# 13hdmi_lcd.net
KiCad netlist of a schematic drawn in Altium Designer
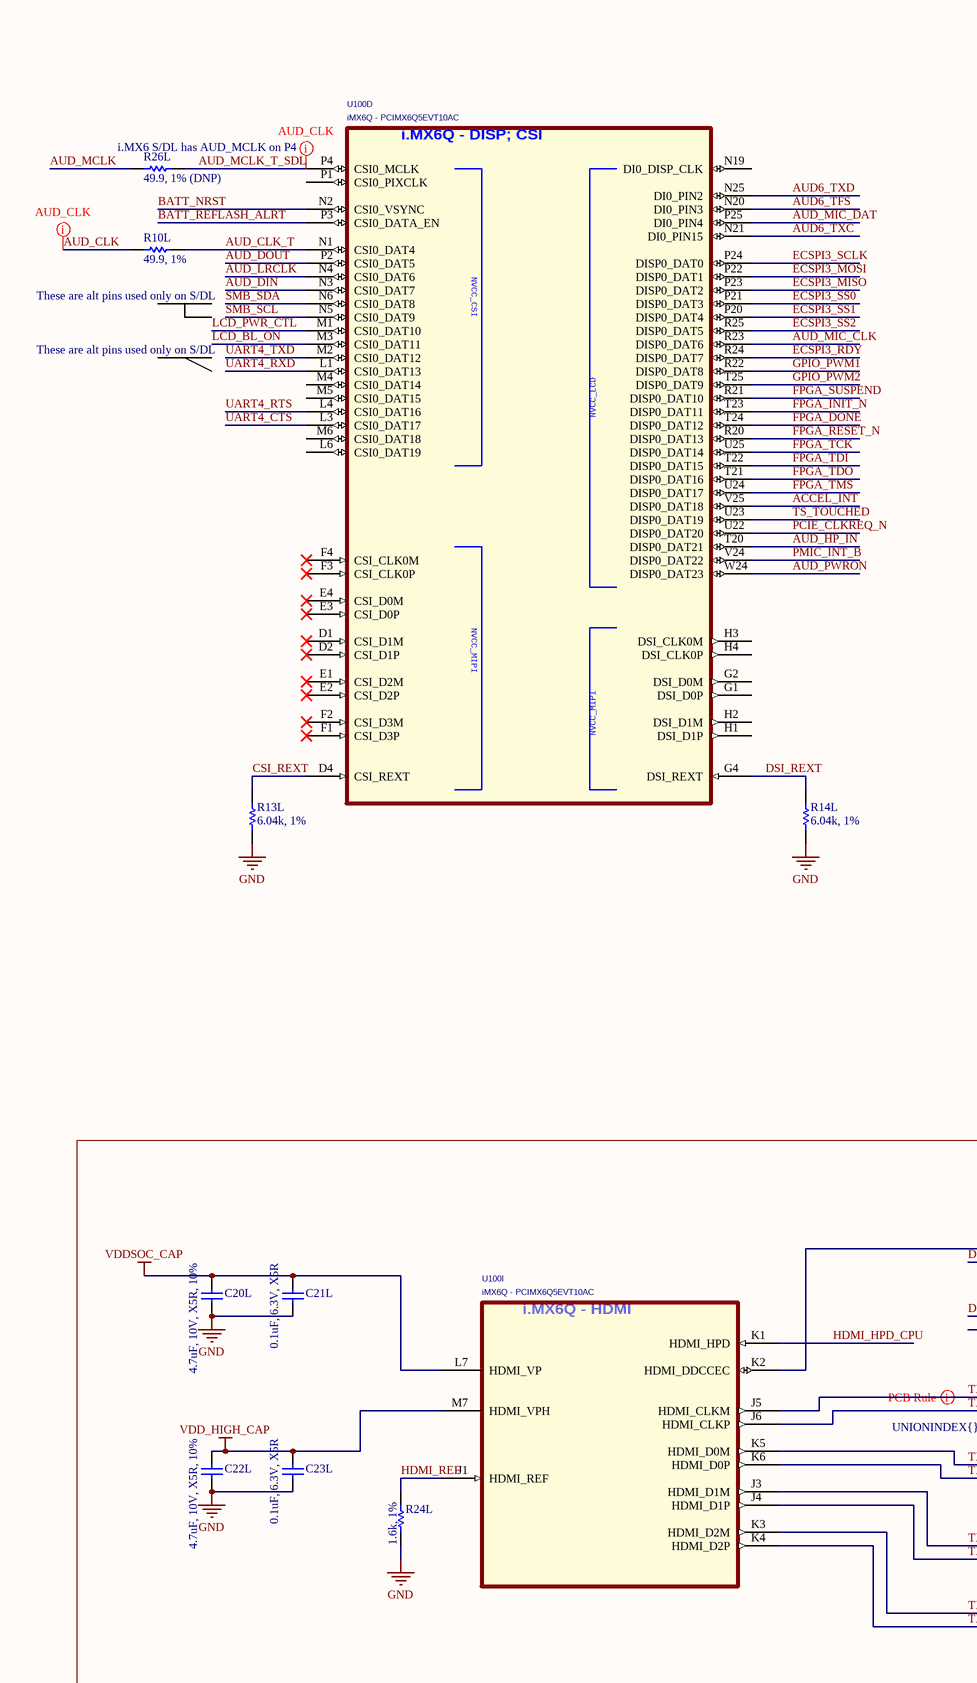
[diagram p0: 13hdmi_lcd.SchDoc, left]
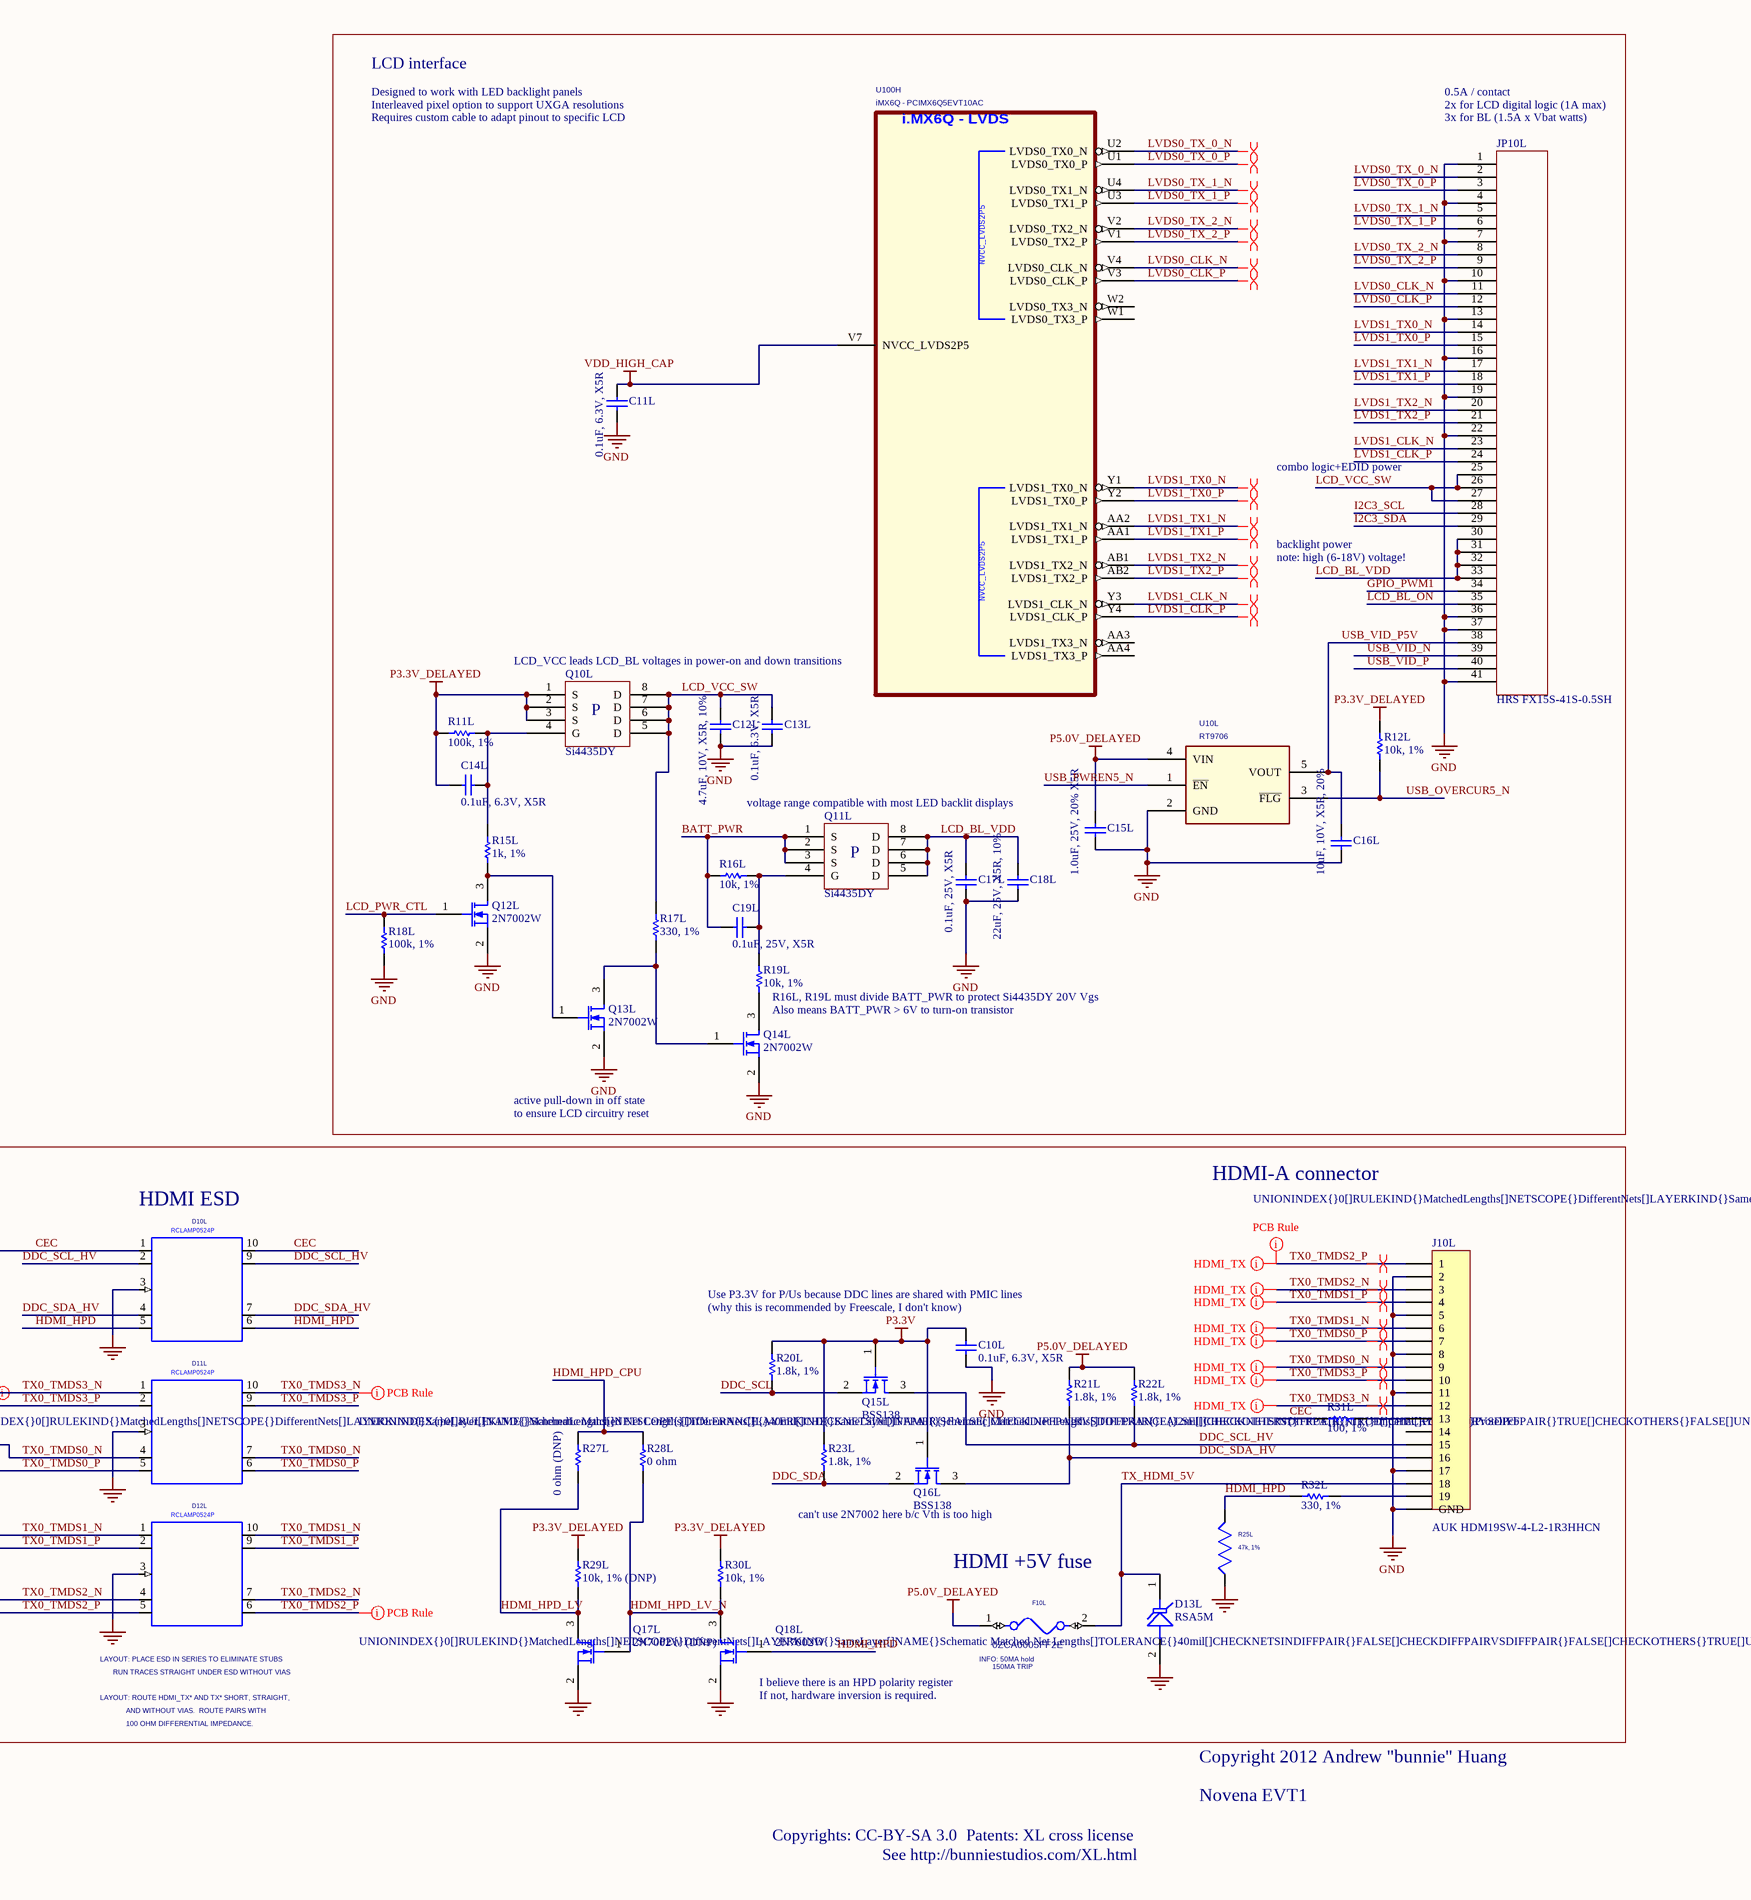
[diagram p1: 13hdmi_lcd.SchDoc, right]

(export (version "E")
  (design (tool "Eeschema 10.0.6"))
  (components
    (comp (ref "C10L")
      (value "0.1uF, 6.3V, X5R")
      (footprint "CAPC0603N_B")
      (description "Capacitor (Semiconductor SIM Model)")
      (fields (field (name "PUBLISHER") "Altium Limited"))
      (libsource (lib "Miscellaneous Devices") (part "Cap Semi"))
    )
    (comp (ref "C11L")
      (value "0.1uF, 6.3V, X5R")
      (footprint "CAPC0603N_B")
      (description "Capacitor (Semiconductor SIM Model)")
      (fields (field (name "PUBLISHER") "Altium Limited"))
      (libsource (lib "Miscellaneous Devices") (part "Cap Semi"))
    )
    (comp (ref "C12L")
      (value "4.7uF, 10V, X5R, 10%")
      (footprint "CAPC1608N")
      (description "Capacitor (Semiconductor SIM Model)")
      (fields (field (name "PUBLISHER") "Altium Limited"))
      (libsource (lib "Miscellaneous Devices") (part "Cap Semi"))
    )
    (comp (ref "C13L")
      (value "0.1uF, 6.3V, X5R")
      (footprint "CAPC0603N_B")
      (description "Capacitor (Semiconductor SIM Model)")
      (fields (field (name "PUBLISHER") "Altium Limited"))
      (libsource (lib "Miscellaneous Devices") (part "Cap Semi"))
    )
    (comp (ref "C14L")
      (value "0.1uF, 6.3V, X5R")
      (footprint "CAPC0603N_B")
      (description "Capacitor (Semiconductor SIM Model)")
      (fields (field (name "PUBLISHER") "Altium Limited"))
      (libsource (lib "Miscellaneous Devices") (part "Cap Semi"))
    )
    (comp (ref "C15L")
      (value "1.0uF, 25V, 20% X5R")
      (footprint "CAPC1608N")
      (description "Capacitor (Semiconductor SIM Model)")
      (fields (field (name "PUBLISHER") "Altium Limited"))
      (libsource (lib "Miscellaneous Devices") (part "Cap Semi"))
    )
    (comp (ref "C16L")
      (value "10uF, 10V, X5R, 20%")
      (footprint "CAPC1608N")
      (description "Capacitor (Semiconductor SIM Model)")
      (fields (field (name "PUBLISHER") "Altium Limited"))
      (libsource (lib "Miscellaneous Devices") (part "Cap Semi"))
    )
    (comp (ref "C17L")
      (value "0.1uF, 25V, X5R")
      (footprint "CAPC1005N")
      (description "Capacitor (Semiconductor SIM Model)")
      (fields (field (name "PUBLISHER") "Altium Limited"))
      (libsource (lib "Miscellaneous Devices") (part "Cap Semi"))
    )
    (comp (ref "C18L")
      (value "22uF, 25V, X5R, 10%")
      (footprint "CAPC3225N")
      (description "Capacitor (Semiconductor SIM Model)")
      (fields (field (name "PUBLISHER") "Altium Limited"))
      (libsource (lib "Miscellaneous Devices") (part "Cap Semi"))
    )
    (comp (ref "C19L")
      (value "0.1uF, 25V, X5R")
      (footprint "CAPC1005N")
      (description "Capacitor (Semiconductor SIM Model)")
      (fields (field (name "PUBLISHER") "Altium Limited"))
      (libsource (lib "Miscellaneous Devices") (part "Cap Semi"))
    )
    (comp (ref "C20L")
      (value "4.7uF, 10V, X5R, 10%")
      (footprint "CAPC1608N_HD")
      (description "Capacitor (Semiconductor SIM Model)")
      (fields (field (name "PUBLISHER") "Altium Limited"))
      (libsource (lib "Miscellaneous Devices") (part "Cap Semi"))
    )
    (comp (ref "C21L")
      (value "0.1uF, 6.3V, X5R")
      (footprint "CAPC0603N_B")
      (description "Capacitor (Semiconductor SIM Model)")
      (fields (field (name "PUBLISHER") "Altium Limited"))
      (libsource (lib "Miscellaneous Devices") (part "Cap Semi"))
    )
    (comp (ref "C22L")
      (value "4.7uF, 10V, X5R, 10%")
      (footprint "CAPC1608N_HD")
      (description "Capacitor (Semiconductor SIM Model)")
      (fields (field (name "PUBLISHER") "Altium Limited"))
      (libsource (lib "Miscellaneous Devices") (part "Cap Semi"))
    )
    (comp (ref "C23L")
      (value "0.1uF, 6.3V, X5R")
      (footprint "CAPC0603N_B")
      (description "Capacitor (Semiconductor SIM Model)")
      (fields (field (name "PUBLISHER") "Altium Limited"))
      (libsource (lib "Miscellaneous Devices") (part "Cap Semi"))
    )
    (comp (ref "D10L")
      (value "RCLAMP0524P")
      (fields (field (name "PART_NUMBER") "V00004-001"))
      (libsource (lib "*") (part "RCLAMP0524P"))
    )
    (comp (ref "D11L")
      (value "RCLAMP0524P")
      (fields (field (name "PART_NUMBER") "V00004-001"))
      (libsource (lib "*") (part "RCLAMP0524P"))
    )
    (comp (ref "D12L")
      (value "RCLAMP0524P")
      (fields (field (name "PART_NUMBER") "V00004-001"))
      (libsource (lib "*") (part "RCLAMP0524P"))
    )
    (comp (ref "D13L")
      (value "RSA5M")
      (footprint "SOD123/X.85")
      (description "Tranzorb")
      (fields (field (name "PUBLISHER") "Altium Limited"))
      (libsource (lib "Miscellaneous Devices") (part "Tranzorb"))
    )
    (comp (ref "F10L")
      (value "0ZCA0005FF2E")
      (description "BelFuse, 50mA hold, 150mA trip")
      (fields (field (name "PART_NUMBER") "M00014-001"))
      (libsource (lib "*") (part "FUSE0805"))
    )
    (comp (ref "J10L")
      (value "AUK HDM19SW-4-L2-1R3HHCN")
      (footprint "MOLEX_47151-0001")
      (description "Molex HDMI connector, Type A")
      (fields (field (name "PUBLISHER") "Altium Limited"))
      (libsource (lib "Miscellaneous Connectors") (part "Header 19"))
    )
    (comp (ref "JP10L")
      (value "HRS FX15S-41S-0.5SH")
      (footprint "HRS_FX15S-41S-0.5SH")
      (description "41-pin header")
      (libsource (lib "commonsch") (part "HRS_FX15S-41S-0.5SH"))
    )
    (comp (ref "Q10L")
      (value "Si4435DY")
      (footprint "SOIC127P600-8AN")
      (description "Singre P-channel FET, 8A, 30V")
      (libsource (lib "commonsch") (part "Si4435DY"))
    )
    (comp (ref "Q11L")
      (value "Si4435DY")
      (footprint "SOIC127P600-8AN")
      (description "Singre P-channel FET, 8A, 30V")
      (libsource (lib "commonsch") (part "Si4435DY"))
    )
    (comp (ref "Q12L")
      (value "2N7002W")
      (footprint "SOT323-3AN")
      (description "N-Channel MOSFET")
      (fields (field (name "PUBLISHER") "Altium Limited"))
      (libsource (lib "Miscellaneous Devices") (part "MOSFET-N"))
    )
    (comp (ref "Q13L")
      (value "2N7002W")
      (footprint "SOT323-3AN")
      (description "N-Channel MOSFET")
      (fields (field (name "PUBLISHER") "Altium Limited"))
      (libsource (lib "Miscellaneous Devices") (part "MOSFET-N"))
    )
    (comp (ref "Q14L")
      (value "2N7002W")
      (footprint "SOT323-3AN")
      (description "N-Channel MOSFET")
      (fields (field (name "PUBLISHER") "Altium Limited"))
      (libsource (lib "Miscellaneous Devices") (part "MOSFET-N"))
    )
    (comp (ref "Q15L")
      (value "BSS138")
      (footprint "SOT23-3N")
      (description "N-Channel MOSFET")
      (fields (field (name "PUBLISHER") "Altium Limited"))
      (libsource (lib "Miscellaneous Devices") (part "MOSFET-N"))
    )
    (comp (ref "Q16L")
      (value "BSS138")
      (footprint "SOT23-3N")
      (description "N-Channel MOSFET")
      (fields (field (name "PUBLISHER") "Altium Limited"))
      (libsource (lib "Miscellaneous Devices") (part "MOSFET-N"))
    )
    (comp (ref "Q17L")
      (value "2N7002W (DNP)")
      (footprint "SOT323-3AN")
      (description "N-Channel MOSFET")
      (fields (field (name "PUBLISHER") "Altium Limited"))
      (libsource (lib "Miscellaneous Devices") (part "MOSFET-N"))
    )
    (comp (ref "Q18L")
      (value "2N7002W")
      (footprint "SOT323-3AN")
      (description "N-Channel MOSFET")
      (fields (field (name "PUBLISHER") "Altium Limited"))
      (libsource (lib "Miscellaneous Devices") (part "MOSFET-N"))
    )
    (comp (ref "R10L")
      (value "49.9, 1%")
      (footprint "RESC1005N")
      (description "Resistor")
      (fields (field (name "PUBLISHER") "Altium Limited"))
      (libsource (lib "Miscellaneous Devices") (part "Res1"))
    )
    (comp (ref "R11L")
      (value "100k, 1%")
      (footprint "RESC1005N")
      (description "Resistor")
      (fields (field (name "PUBLISHER") "Altium Limited"))
      (libsource (lib "Miscellaneous Devices") (part "Res1"))
    )
    (comp (ref "R12L")
      (value "10k, 1%")
      (footprint "RESC1005N")
      (description "Resistor")
      (fields (field (name "PUBLISHER") "Altium Limited"))
      (libsource (lib "Miscellaneous Devices") (part "Res1"))
    )
    (comp (ref "R13L")
      (value "6.04k, 1%")
      (footprint "RESC1005N")
      (description "Resistor")
      (fields (field (name "PUBLISHER") "Altium Limited"))
      (libsource (lib "Miscellaneous Devices") (part "Res1"))
    )
    (comp (ref "R14L")
      (value "6.04k, 1%")
      (footprint "RESC1005N")
      (description "Resistor")
      (fields (field (name "PUBLISHER") "Altium Limited"))
      (libsource (lib "Miscellaneous Devices") (part "Res1"))
    )
    (comp (ref "R15L")
      (value "1k, 1%")
      (footprint "RESC1005N")
      (description "Resistor")
      (fields (field (name "PUBLISHER") "Altium Limited"))
      (libsource (lib "Miscellaneous Devices") (part "Res1"))
    )
    (comp (ref "R16L")
      (value "10k, 1%")
      (footprint "RESC1005N")
      (description "Resistor")
      (fields (field (name "PUBLISHER") "Altium Limited"))
      (libsource (lib "Miscellaneous Devices") (part "Res1"))
    )
    (comp (ref "R17L")
      (value "330, 1%")
      (footprint "RESC1005N")
      (description "Resistor")
      (fields (field (name "PUBLISHER") "Altium Limited"))
      (libsource (lib "Miscellaneous Devices") (part "Res1"))
    )
    (comp (ref "R18L")
      (value "100k, 1%")
      (footprint "RESC1005N")
      (description "Resistor")
      (fields (field (name "PUBLISHER") "Altium Limited"))
      (libsource (lib "Miscellaneous Devices") (part "Res1"))
    )
    (comp (ref "R19L")
      (value "10k, 1%")
      (footprint "RESC1005N")
      (description "Resistor")
      (fields (field (name "PUBLISHER") "Altium Limited"))
      (libsource (lib "Miscellaneous Devices") (part "Res1"))
    )
    (comp (ref "R20L")
      (value "1.8k, 1%")
      (footprint "RESC1005N")
      (description "Resistor")
      (fields (field (name "PUBLISHER") "Altium Limited"))
      (libsource (lib "Miscellaneous Devices") (part "Res1"))
    )
    (comp (ref "R21L")
      (value "1.8k, 1%")
      (footprint "RESC1005N")
      (description "Resistor")
      (fields (field (name "PUBLISHER") "Altium Limited"))
      (libsource (lib "Miscellaneous Devices") (part "Res1"))
    )
    (comp (ref "R22L")
      (value "1.8k, 1%")
      (footprint "RESC1005N")
      (description "Resistor")
      (fields (field (name "PUBLISHER") "Altium Limited"))
      (libsource (lib "Miscellaneous Devices") (part "Res1"))
    )
    (comp (ref "R23L")
      (value "1.8k, 1%")
      (footprint "RESC1005N")
      (description "Resistor")
      (fields (field (name "PUBLISHER") "Altium Limited"))
      (libsource (lib "Miscellaneous Devices") (part "Res1"))
    )
    (comp (ref "R24L")
      (value "1.6k, 1%")
      (footprint "RESC1005N")
      (description "Resistor")
      (fields (field (name "PUBLISHER") "Altium Limited"))
      (libsource (lib "Miscellaneous Devices") (part "Res1"))
    )
    (comp (ref "R25L")
      (value "47k, 1%")
      (fields (field (name "PART_NUMBER") "D13015-001") (field (name "MFG") "PANASONIC"))
      (libsource (lib "*") (part "RES#1"))
    )
    (comp (ref "R26L")
      (value "49.9, 1% (DNP)")
      (footprint "RESC1005N")
      (description "Resistor")
      (fields (field (name "PUBLISHER") "Altium Limited"))
      (libsource (lib "Miscellaneous Devices") (part "Res1"))
    )
    (comp (ref "R27L")
      (value "0 ohm (DNP)")
      (footprint "RESC1005N")
      (description "Resistor")
      (fields (field (name "PUBLISHER") "Altium Limited"))
      (libsource (lib "Miscellaneous Devices") (part "Res1"))
    )
    (comp (ref "R28L")
      (value "0 ohm")
      (footprint "RESC1005N")
      (description "Resistor")
      (fields (field (name "PUBLISHER") "Altium Limited"))
      (libsource (lib "Miscellaneous Devices") (part "Res1"))
    )
    (comp (ref "R29L")
      (value "10k, 1% (DNP)")
      (footprint "RESC1005N")
      (description "Resistor")
      (fields (field (name "PUBLISHER") "Altium Limited"))
      (libsource (lib "Miscellaneous Devices") (part "Res1"))
    )
    (comp (ref "R30L")
      (value "10k, 1%")
      (footprint "RESC1005N")
      (description "Resistor")
      (fields (field (name "PUBLISHER") "Altium Limited"))
      (libsource (lib "Miscellaneous Devices") (part "Res1"))
    )
    (comp (ref "R31L")
      (value "100, 1%")
      (footprint "RESC1005N")
      (description "Resistor")
      (fields (field (name "PUBLISHER") "Altium Limited"))
      (libsource (lib "Miscellaneous Devices") (part "Res1"))
    )
    (comp (ref "R32L")
      (value "330, 1%")
      (footprint "RESC1005N")
      (description "Resistor")
      (fields (field (name "PUBLISHER") "Altium Limited"))
      (libsource (lib "Miscellaneous Devices") (part "Res1"))
    )
    (comp (ref "U10L")
      (value "RT9706")
      (description "IC LIN SW W/FLAG 500MA 2.0-5.5V SOT23-5")
      (libsource (lib "*") (part "RT9706"))
    )
    (comp (ref "U100")
      (value "iMX6Q - PCIMX6Q5EVT10AC")
      (description "PLACEHOLDER FOR FREESCALE PART NUMBER PMCIMX6Q6VV1A.")
      (libsource (lib "*") (part "PCIMX6Q6VV1A"))
    )
  )
  (nets
    (net (code "1") (name "/ACCEL_INT") (class "Default")
      (node (ref "U100") (pin "V25") (pinfunction "DISP0_DAT18_V25") (pintype "bidirectional"))
    )
    (net (code "2") (name "/AUD6_TFS") (class "Default")
      (node (ref "U100") (pin "N20") (pinfunction "DI0_PIN3_N20") (pintype "bidirectional"))
    )
    (net (code "3") (name "/AUD6_TXC") (class "Default")
      (node (ref "U100") (pin "N21") (pinfunction "DI0_PIN15_N21") (pintype "bidirectional"))
    )
    (net (code "4") (name "/AUD6_TXD") (class "Default")
      (node (ref "U100") (pin "N25") (pinfunction "DI0_PIN2_N25") (pintype "bidirectional"))
    )
    (net (code "5") (name "/AUD_CLK") (class "Default")
      (node (ref "R10L") (pin "2") (pinfunction "2_2") (pintype "passive"))
    )
    (net (code "6") (name "/AUD_CLK_T") (class "Default")
      (node (ref "R10L") (pin "1") (pinfunction "1_1") (pintype "passive"))
      (node (ref "U100") (pin "N1") (pinfunction "CSI0_DAT4_N1") (pintype "bidirectional"))
    )
    (net (code "7") (name "/AUD_DIN") (class "Default")
      (node (ref "U100") (pin "N3") (pinfunction "CSI0_DAT7_N3") (pintype "bidirectional"))
    )
    (net (code "8") (name "/AUD_DOUT") (class "Default")
      (node (ref "U100") (pin "P2") (pinfunction "CSI0_DAT5_P2") (pintype "bidirectional"))
    )
    (net (code "9") (name "/AUD_HP_IN") (class "Default")
      (node (ref "U100") (pin "T20") (pinfunction "DISP0_DAT21_T20") (pintype "bidirectional"))
    )
    (net (code "10") (name "/AUD_LRCLK") (class "Default")
      (node (ref "U100") (pin "N4") (pinfunction "CSI0_DAT6_N4") (pintype "bidirectional"))
    )
    (net (code "11") (name "/AUD_MCLK") (class "Default")
      (node (ref "R26L") (pin "2") (pinfunction "2_2") (pintype "passive"))
    )
    (net (code "12") (name "/AUD_MCLK_T_SDL") (class "Default")
      (node (ref "R26L") (pin "1") (pinfunction "1_1") (pintype "passive"))
      (node (ref "U100") (pin "P4") (pinfunction "CSI0_MCLK_P4") (pintype "bidirectional"))
    )
    (net (code "13") (name "/AUD_MIC_CLK") (class "Default")
      (node (ref "U100") (pin "R23") (pinfunction "DISP0_DAT6_R23") (pintype "bidirectional"))
    )
    (net (code "14") (name "/AUD_MIC_DAT") (class "Default")
      (node (ref "U100") (pin "P25") (pinfunction "DI0_PIN4_P25") (pintype "bidirectional"))
    )
    (net (code "15") (name "/AUD_PWRON") (class "Default")
      (node (ref "U100") (pin "W24") (pinfunction "DISP0_DAT23_W24") (pintype "bidirectional"))
    )
    (net (code "16") (name "/BATT_NRST") (class "Default")
      (node (ref "U100") (pin "N2") (pinfunction "CSI0_VSYNC_N2") (pintype "bidirectional"))
    )
    (net (code "17") (name "/BATT_PWR") (class "Default")
      (node (ref "C19L") (pin "1") (pinfunction "1_1") (pintype "passive"))
      (node (ref "Q11L") (pin "1") (pinfunction "S_1") (pintype "passive"))
      (node (ref "Q11L") (pin "2") (pinfunction "S_2") (pintype "passive"))
      (node (ref "Q11L") (pin "3") (pinfunction "S_3") (pintype "passive"))
      (node (ref "R16L") (pin "2") (pinfunction "2_2") (pintype "passive"))
    )
    (net (code "18") (name "/BATT_REFLASH_ALRT") (class "Default")
      (node (ref "U100") (pin "P3") (pinfunction "CSI0_DATA_EN_P3") (pintype "bidirectional"))
    )
    (net (code "19") (name "/CEC") (class "Default")
      (node (ref "D10L") (pin "1") (pinfunction "IO1A_1") (pintype "bidirectional"))
      (node (ref "D10L") (pin "10") (pinfunction "IO1B_10") (pintype "bidirectional"))
      (node (ref "R31L") (pin "2") (pinfunction "2_2") (pintype "passive"))
      (node (ref "U100") (pin "K2") (pinfunction "HDMI_DDCCEC_K2") (pintype "bidirectional"))
    )
    (net (code "20") (name "/CSI_REXT") (class "Default")
      (node (ref "R13L") (pin "1") (pinfunction "1_1") (pintype "passive"))
      (node (ref "U100") (pin "D4") (pinfunction "CSI_REXT_D4") (pintype "input"))
    )
    (net (code "21") (name "/DDC_SCL") (class "Default")
      (node (ref "Q15L") (pin "2") (pinfunction "S_2") (pintype "passive"))
      (node (ref "R20L") (pin "2") (pinfunction "2_2") (pintype "passive"))
    )
    (net (code "22") (name "/DDC_SCL_HV") (class "Default")
      (node (ref "D10L") (pin "2") (pinfunction "IO2A_2") (pintype "bidirectional"))
      (node (ref "D10L") (pin "9") (pinfunction "IO2B_9") (pintype "bidirectional"))
      (node (ref "J10L") (pin "15") (pinfunction "15_15") (pintype "passive"))
      (node (ref "Q15L") (pin "3") (pinfunction "D_3") (pintype "passive"))
      (node (ref "R22L") (pin "2") (pinfunction "2_2") (pintype "passive"))
    )
    (net (code "23") (name "/DDC_SDA") (class "Default")
      (node (ref "Q16L") (pin "2") (pinfunction "S_2") (pintype "passive"))
      (node (ref "R23L") (pin "2") (pinfunction "2_2") (pintype "passive"))
    )
    (net (code "24") (name "/DDC_SDA_HV") (class "Default")
      (node (ref "D10L") (pin "4") (pinfunction "IO3A_4") (pintype "bidirectional"))
      (node (ref "D10L") (pin "7") (pinfunction "IO3B_7") (pintype "bidirectional"))
      (node (ref "J10L") (pin "16") (pinfunction "16_16") (pintype "passive"))
      (node (ref "Q16L") (pin "3") (pinfunction "D_3") (pintype "passive"))
      (node (ref "R21L") (pin "2") (pinfunction "2_2") (pintype "passive"))
    )
    (net (code "25") (name "/DSI_REXT") (class "Default")
      (node (ref "R14L") (pin "1") (pinfunction "1_1") (pintype "passive"))
      (node (ref "U100") (pin "G4") (pinfunction "DSI_REXT_G4") (pintype "input"))
    )
    (net (code "26") (name "/ECSPI3_MISO") (class "Default")
      (node (ref "U100") (pin "P23") (pinfunction "DISP0_DAT2_P23") (pintype "bidirectional"))
    )
    (net (code "27") (name "/ECSPI3_MOSI") (class "Default")
      (node (ref "U100") (pin "P22") (pinfunction "DISP0_DAT1_P22") (pintype "bidirectional"))
    )
    (net (code "28") (name "/ECSPI3_RDY") (class "Default")
      (node (ref "U100") (pin "R24") (pinfunction "DISP0_DAT7_R24") (pintype "bidirectional"))
    )
    (net (code "29") (name "/ECSPI3_SCLK") (class "Default")
      (node (ref "U100") (pin "P24") (pinfunction "DISP0_DAT0_P24") (pintype "bidirectional"))
    )
    (net (code "30") (name "/ECSPI3_SS0") (class "Default")
      (node (ref "U100") (pin "P21") (pinfunction "DISP0_DAT3_P21") (pintype "bidirectional"))
    )
    (net (code "31") (name "/ECSPI3_SS1") (class "Default")
      (node (ref "U100") (pin "P20") (pinfunction "DISP0_DAT4_P20") (pintype "bidirectional"))
    )
    (net (code "32") (name "/ECSPI3_SS2") (class "Default")
      (node (ref "U100") (pin "R25") (pinfunction "DISP0_DAT5_R25") (pintype "bidirectional"))
    )
    (net (code "33") (name "/FPGA_DONE") (class "Default")
      (node (ref "U100") (pin "T24") (pinfunction "DISP0_DAT12_T24") (pintype "bidirectional"))
    )
    (net (code "34") (name "/FPGA_INIT_N") (class "Default")
      (node (ref "U100") (pin "T23") (pinfunction "DISP0_DAT11_T23") (pintype "bidirectional"))
    )
    (net (code "35") (name "/FPGA_RESET_N") (class "Default")
      (node (ref "U100") (pin "R20") (pinfunction "DISP0_DAT13_R20") (pintype "bidirectional"))
    )
    (net (code "36") (name "/FPGA_SUSPEND") (class "Default")
      (node (ref "U100") (pin "R21") (pinfunction "DISP0_DAT10_R21") (pintype "bidirectional"))
    )
    (net (code "37") (name "/FPGA_TCK") (class "Default")
      (node (ref "U100") (pin "U25") (pinfunction "DISP0_DAT14_U25") (pintype "bidirectional"))
    )
    (net (code "38") (name "/FPGA_TDI") (class "Default")
      (node (ref "U100") (pin "T22") (pinfunction "DISP0_DAT15_T22") (pintype "bidirectional"))
    )
    (net (code "39") (name "/FPGA_TDO") (class "Default")
      (node (ref "U100") (pin "T21") (pinfunction "DISP0_DAT16_T21") (pintype "bidirectional"))
    )
    (net (code "40") (name "/FPGA_TMS") (class "Default")
      (node (ref "U100") (pin "U24") (pinfunction "DISP0_DAT17_U24") (pintype "bidirectional"))
    )
    (net (code "41") (name "/GPIO_PWM1") (class "Default")
      (node (ref "JP10L") (pin "34") (pintype "passive"))
      (node (ref "U100") (pin "R22") (pinfunction "DISP0_DAT8_R22") (pintype "bidirectional"))
    )
    (net (code "42") (name "/GPIO_PWM2") (class "Default")
      (node (ref "U100") (pin "T25") (pinfunction "DISP0_DAT9_T25") (pintype "bidirectional"))
    )
    (net (code "43") (name "/HDMI_HPD") (class "Default")
      (node (ref "D10L") (pin "5") (pinfunction "IO4A_5") (pintype "bidirectional"))
      (node (ref "D10L") (pin "6") (pinfunction "IO4B_6") (pintype "bidirectional"))
      (node (ref "Q18L") (pin "1") (pinfunction "G_1") (pintype "passive"))
      (node (ref "R25L") (pin "1") (pinfunction "A_1") (pintype "bidirectional"))
      (node (ref "R32L") (pin "2") (pinfunction "2_2") (pintype "passive"))
    )
    (net (code "44") (name "/HDMI_HPD_CPU") (class "Default")
      (node (ref "R27L") (pin "1") (pinfunction "1_1") (pintype "passive"))
      (node (ref "R28L") (pin "1") (pinfunction "1_1") (pintype "passive"))
      (node (ref "U100") (pin "K1") (pinfunction "HDMI_HPD_K1") (pintype "input"))
    )
    (net (code "45") (name "/HDMI_HPD_LV") (class "Default")
      (node (ref "Q17L") (pin "3") (pinfunction "D_3") (pintype "passive"))
      (node (ref "R27L") (pin "2") (pinfunction "2_2") (pintype "passive"))
      (node (ref "R29L") (pin "2") (pinfunction "2_2") (pintype "passive"))
    )
    (net (code "46") (name "/HDMI_HPD_LV_N") (class "Default")
      (node (ref "Q17L") (pin "1") (pinfunction "G_1") (pintype "passive"))
      (node (ref "Q18L") (pin "3") (pinfunction "D_3") (pintype "passive"))
      (node (ref "R28L") (pin "2") (pinfunction "2_2") (pintype "passive"))
      (node (ref "R30L") (pin "2") (pinfunction "2_2") (pintype "passive"))
    )
    (net (code "47") (name "/HDMI_REF") (class "Default")
      (node (ref "R24L") (pin "2") (pinfunction "2_2") (pintype "passive"))
      (node (ref "U100") (pin "J1") (pinfunction "HDMI_REF_J1") (pintype "input"))
    )
    (net (code "48") (name "/I2C3_SCL") (class "Default") (node (ref "JP10L") (pin "28") (pintype "passive")))
    (net (code "49") (name "/I2C3_SDA") (class "Default") (node (ref "JP10L") (pin "29") (pintype "passive")))
    (net (code "50") (name "/LCD_BL_ON") (class "Default")
      (node (ref "JP10L") (pin "35") (pintype "passive"))
      (node (ref "U100") (pin "M3") (pinfunction "CSI0_DAT11_M3") (pintype "bidirectional"))
    )
    (net (code "51") (name "/LCD_BL_VDD") (class "Default")
      (node (ref "C17L") (pin "1") (pinfunction "1_1") (pintype "passive"))
      (node (ref "C18L") (pin "1") (pinfunction "1_1") (pintype "passive"))
      (node (ref "JP10L") (pin "30") (pintype "passive"))
      (node (ref "JP10L") (pin "31") (pintype "passive"))
      (node (ref "JP10L") (pin "32") (pintype "passive"))
      (node (ref "JP10L") (pin "33") (pintype "passive"))
      (node (ref "Q11L") (pin "5") (pinfunction "D_5") (pintype "passive"))
      (node (ref "Q11L") (pin "6") (pinfunction "D_6") (pintype "passive"))
      (node (ref "Q11L") (pin "7") (pinfunction "D_7") (pintype "passive"))
      (node (ref "Q11L") (pin "8") (pinfunction "D_8") (pintype "passive"))
    )
    (net (code "52") (name "/LCD_PWR_CTL") (class "Default")
      (node (ref "Q12L") (pin "1") (pinfunction "G_1") (pintype "passive"))
      (node (ref "R18L") (pin "2") (pinfunction "2_2") (pintype "passive"))
      (node (ref "U100") (pin "M1") (pinfunction "CSI0_DAT10_M1") (pintype "bidirectional"))
    )
    (net (code "53") (name "/LCD_VCC_SW") (class "Default")
      (node (ref "C12L") (pin "1") (pinfunction "1_1") (pintype "passive"))
      (node (ref "C13L") (pin "1") (pinfunction "1_1") (pintype "passive"))
      (node (ref "JP10L") (pin "25") (pintype "passive"))
      (node (ref "JP10L") (pin "26") (pintype "passive"))
      (node (ref "JP10L") (pin "27") (pintype "passive"))
      (node (ref "Q10L") (pin "5") (pinfunction "D_5") (pintype "passive"))
      (node (ref "Q10L") (pin "6") (pinfunction "D_6") (pintype "passive"))
      (node (ref "Q10L") (pin "7") (pinfunction "D_7") (pintype "passive"))
      (node (ref "Q10L") (pin "8") (pinfunction "D_8") (pintype "passive"))
      (node (ref "R17L") (pin "2") (pinfunction "2_2") (pintype "passive"))
    )
    (net (code "54") (name "/LVDS0_CLK_N") (class "Default")
      (node (ref "JP10L") (pin "11") (pintype "passive"))
      (node (ref "U100") (pin "V4") (pinfunction "LVDS0_CLK_N_V4") (pintype "output"))
    )
    (net (code "55") (name "/LVDS0_CLK_P") (class "Default")
      (node (ref "JP10L") (pin "12") (pintype "passive"))
      (node (ref "U100") (pin "V3") (pinfunction "LVDS0_CLK_P_V3") (pintype "output"))
    )
    (net (code "56") (name "/LVDS0_TX_0_N") (class "Default")
      (node (ref "JP10L") (pin "2") (pintype "passive"))
      (node (ref "U100") (pin "U2") (pinfunction "LVDS0_TX0_N_U2") (pintype "output"))
    )
    (net (code "57") (name "/LVDS0_TX_0_P") (class "Default")
      (node (ref "JP10L") (pin "3") (pintype "passive"))
      (node (ref "U100") (pin "U1") (pinfunction "LVDS0_TX0_P_U1") (pintype "output"))
    )
    (net (code "58") (name "/LVDS0_TX_1_N") (class "Default")
      (node (ref "JP10L") (pin "5") (pintype "passive"))
      (node (ref "U100") (pin "U4") (pinfunction "LVDS0_TX1_N_U4") (pintype "output"))
    )
    (net (code "59") (name "/LVDS0_TX_1_P") (class "Default")
      (node (ref "JP10L") (pin "6") (pintype "passive"))
      (node (ref "U100") (pin "U3") (pinfunction "LVDS0_TX1_P_U3") (pintype "output"))
    )
    (net (code "60") (name "/LVDS0_TX_2_N") (class "Default")
      (node (ref "JP10L") (pin "8") (pintype "passive"))
      (node (ref "U100") (pin "V2") (pinfunction "LVDS0_TX2_N_V2") (pintype "output"))
    )
    (net (code "61") (name "/LVDS0_TX_2_P") (class "Default")
      (node (ref "JP10L") (pin "9") (pintype "passive"))
      (node (ref "U100") (pin "V1") (pinfunction "LVDS0_TX2_P_V1") (pintype "output"))
    )
    (net (code "62") (name "/LVDS1_CLK_N") (class "Default")
      (node (ref "JP10L") (pin "23") (pintype "passive"))
      (node (ref "U100") (pin "Y3") (pinfunction "LVDS1_CLK_N_Y3") (pintype "output"))
    )
    (net (code "63") (name "/LVDS1_CLK_P") (class "Default")
      (node (ref "JP10L") (pin "24") (pintype "passive"))
      (node (ref "U100") (pin "Y4") (pinfunction "LVDS1_CLK_P_Y4") (pintype "output"))
    )
    (net (code "64") (name "/LVDS1_TX0_N") (class "Default")
      (node (ref "JP10L") (pin "14") (pintype "passive"))
      (node (ref "U100") (pin "Y1") (pinfunction "LVDS1_TX0_N_Y1") (pintype "output"))
    )
    (net (code "65") (name "/LVDS1_TX0_P") (class "Default")
      (node (ref "JP10L") (pin "15") (pintype "passive"))
      (node (ref "U100") (pin "Y2") (pinfunction "LVDS1_TX0_P_Y2") (pintype "output"))
    )
    (net (code "66") (name "/LVDS1_TX1_N") (class "Default")
      (node (ref "JP10L") (pin "17") (pintype "passive"))
      (node (ref "U100") (pin "AA2") (pinfunction "LVDS1_TX1_N_AA2") (pintype "output"))
    )
    (net (code "67") (name "/LVDS1_TX1_P") (class "Default")
      (node (ref "JP10L") (pin "18") (pintype "passive"))
      (node (ref "U100") (pin "AA1") (pinfunction "LVDS1_TX1_P_AA1") (pintype "output"))
    )
    (net (code "68") (name "/LVDS1_TX2_N") (class "Default")
      (node (ref "JP10L") (pin "20") (pintype "passive"))
      (node (ref "U100") (pin "AB1") (pinfunction "LVDS1_TX2_N_AB1") (pintype "output"))
    )
    (net (code "69") (name "/LVDS1_TX2_P") (class "Default")
      (node (ref "JP10L") (pin "21") (pintype "passive"))
      (node (ref "U100") (pin "AB2") (pinfunction "LVDS1_TX2_P_AB2") (pintype "output"))
    )
    (net (code "70") (name "/PCIE_CLKREQ_N") (class "Default")
      (node (ref "U100") (pin "U22") (pinfunction "DISP0_DAT20_U22") (pintype "bidirectional"))
    )
    (net (code "71") (name "/PMIC_INT_B") (class "Default")
      (node (ref "U100") (pin "V24") (pinfunction "DISP0_DAT22_V24") (pintype "bidirectional"))
    )
    (net (code "72") (name "/SMB_SCL") (class "Default")
      (node (ref "U100") (pin "N5") (pinfunction "CSI0_DAT9_N5") (pintype "bidirectional"))
    )
    (net (code "73") (name "/SMB_SDA") (class "Default")
      (node (ref "U100") (pin "N6") (pinfunction "CSI0_DAT8_N6") (pintype "bidirectional"))
    )
    (net (code "74") (name "/TS_TOUCHED") (class "Default")
      (node (ref "U100") (pin "U23") (pinfunction "DISP0_DAT19_U23") (pintype "bidirectional"))
    )
    (net (code "75") (name "/TX0_TMDS0_N") (class "Default")
      (node (ref "D11L") (pin "4") (pinfunction "IO3A_4") (pintype "bidirectional"))
      (node (ref "D11L") (pin "7") (pinfunction "IO3B_7") (pintype "bidirectional"))
      (node (ref "J10L") (pin "9") (pinfunction "9_9") (pintype "passive"))
      (node (ref "U100") (pin "K5") (pinfunction "HDMI_D0M_K5") (pintype "output"))
    )
    (net (code "76") (name "/TX0_TMDS0_P") (class "Default")
      (node (ref "D11L") (pin "5") (pinfunction "IO4A_5") (pintype "bidirectional"))
      (node (ref "D11L") (pin "6") (pinfunction "IO4B_6") (pintype "bidirectional"))
      (node (ref "J10L") (pin "7") (pinfunction "7_7") (pintype "passive"))
      (node (ref "U100") (pin "K6") (pinfunction "HDMI_D0P_K6") (pintype "output"))
    )
    (net (code "77") (name "/TX0_TMDS1_N") (class "Default")
      (node (ref "D12L") (pin "1") (pinfunction "IO1A_1") (pintype "bidirectional"))
      (node (ref "D12L") (pin "10") (pinfunction "IO1B_10") (pintype "bidirectional"))
      (node (ref "J10L") (pin "6") (pinfunction "6_6") (pintype "passive"))
      (node (ref "U100") (pin "J3") (pinfunction "HDMI_D1M_J3") (pintype "output"))
    )
    (net (code "78") (name "/TX0_TMDS1_P") (class "Default")
      (node (ref "D12L") (pin "2") (pinfunction "IO2A_2") (pintype "bidirectional"))
      (node (ref "D12L") (pin "9") (pinfunction "IO2B_9") (pintype "bidirectional"))
      (node (ref "J10L") (pin "4") (pinfunction "4_4") (pintype "passive"))
      (node (ref "U100") (pin "J4") (pinfunction "HDMI_D1P_J4") (pintype "output"))
    )
    (net (code "79") (name "/TX0_TMDS2_N") (class "Default")
      (node (ref "D12L") (pin "4") (pinfunction "IO3A_4") (pintype "bidirectional"))
      (node (ref "D12L") (pin "7") (pinfunction "IO3B_7") (pintype "bidirectional"))
      (node (ref "J10L") (pin "3") (pinfunction "3_3") (pintype "passive"))
      (node (ref "U100") (pin "K3") (pinfunction "HDMI_D2M_K3") (pintype "output"))
    )
    (net (code "80") (name "/TX0_TMDS2_P") (class "Default")
      (node (ref "D12L") (pin "5") (pinfunction "IO4A_5") (pintype "bidirectional"))
      (node (ref "D12L") (pin "6") (pinfunction "IO4B_6") (pintype "bidirectional"))
      (node (ref "J10L") (pin "1") (pinfunction "1_1") (pintype "passive"))
      (node (ref "U100") (pin "K4") (pinfunction "HDMI_D2P_K4") (pintype "output"))
    )
    (net (code "81") (name "/TX0_TMDS3_N") (class "Default")
      (node (ref "D11L") (pin "1") (pinfunction "IO1A_1") (pintype "bidirectional"))
      (node (ref "D11L") (pin "10") (pinfunction "IO1B_10") (pintype "bidirectional"))
      (node (ref "J10L") (pin "12") (pinfunction "12_12") (pintype "passive"))
      (node (ref "U100") (pin "J5") (pinfunction "HDMI_CLKM_J5") (pintype "output"))
    )
    (net (code "82") (name "/TX0_TMDS3_P") (class "Default")
      (node (ref "D11L") (pin "2") (pinfunction "IO2A_2") (pintype "bidirectional"))
      (node (ref "D11L") (pin "9") (pinfunction "IO2B_9") (pintype "bidirectional"))
      (node (ref "J10L") (pin "10") (pinfunction "10_10") (pintype "passive"))
      (node (ref "U100") (pin "J6") (pinfunction "HDMI_CLKP_J6") (pintype "output"))
    )
    (net (code "83") (name "/TX_HDMI_5V") (class "Default")
      (node (ref "D13L") (pin "1") (pinfunction "K_1") (pintype "passive"))
      (node (ref "F10L") (pin "2") (pinfunction "2_2") (pintype "bidirectional"))
      (node (ref "J10L") (pin "18") (pinfunction "18_18") (pintype "passive"))
    )
    (net (code "84") (name "/UART4_CTS") (class "Default")
      (node (ref "U100") (pin "L3") (pinfunction "CSI0_DAT17_L3") (pintype "bidirectional"))
    )
    (net (code "85") (name "/UART4_RTS") (class "Default")
      (node (ref "U100") (pin "L4") (pinfunction "CSI0_DAT16_L4") (pintype "bidirectional"))
    )
    (net (code "86") (name "/UART4_RXD") (class "Default")
      (node (ref "U100") (pin "L1") (pinfunction "CSI0_DAT13_L1") (pintype "bidirectional"))
    )
    (net (code "87") (name "/UART4_TXD") (class "Default")
      (node (ref "U100") (pin "M2") (pinfunction "CSI0_DAT12_M2") (pintype "bidirectional"))
    )
    (net (code "88") (name "/USB_OVERCUR5_N") (class "Default")
      (node (ref "R12L") (pin "1") (pinfunction "1_1") (pintype "passive"))
      (node (ref "U10L") (pin "3") (pinfunction "~{FLG}_3") (pintype "passive"))
    )
    (net (code "89") (name "/USB_PWREN5_N") (class "Default")
      (node (ref "U10L") (pin "1") (pinfunction "~{EN}_1") (pintype "passive"))
    )
    (net (code "90") (name "/USB_VID_N") (class "Default")
      (node (ref "JP10L") (pin "39") (pintype "passive"))
    )
    (net (code "91") (name "/USB_VID_P") (class "Default")
      (node (ref "JP10L") (pin "40") (pintype "passive"))
    )
    (net (code "92") (name "/USB_VID_P5V") (class "Default")
      (node (ref "C16L") (pin "1") (pinfunction "1_1") (pintype "passive"))
      (node (ref "JP10L") (pin "38") (pintype "passive"))
      (node (ref "U10L") (pin "5") (pinfunction "VOUT_5") (pintype "passive"))
    )
    (net (code "93") (name "GND") (class "Default")
      (node (ref "C10L") (pin "2") (pinfunction "2_2") (pintype "passive"))
      (node (ref "C11L") (pin "2") (pinfunction "2_2") (pintype "passive"))
      (node (ref "C12L") (pin "2") (pinfunction "2_2") (pintype "passive"))
      (node (ref "C13L") (pin "2") (pinfunction "2_2") (pintype "passive"))
      (node (ref "C15L") (pin "2") (pinfunction "2_2") (pintype "passive"))
      (node (ref "C16L") (pin "2") (pinfunction "2_2") (pintype "passive"))
      (node (ref "C17L") (pin "2") (pinfunction "2_2") (pintype "passive"))
      (node (ref "C18L") (pin "2") (pinfunction "2_2") (pintype "passive"))
      (node (ref "C20L") (pin "2") (pinfunction "2_2") (pintype "passive"))
      (node (ref "C21L") (pin "2") (pinfunction "2_2") (pintype "passive"))
      (node (ref "C22L") (pin "2") (pinfunction "2_2") (pintype "passive"))
      (node (ref "C23L") (pin "2") (pinfunction "2_2") (pintype "passive"))
      (node (ref "D10L") (pin "3") (pinfunction "GND1_3") (pintype "input"))
      (node (ref "D11L") (pin "3") (pinfunction "GND1_3") (pintype "input"))
      (node (ref "D12L") (pin "3") (pinfunction "GND1_3") (pintype "input"))
      (node (ref "D13L") (pin "2") (pinfunction "A_2") (pintype "passive"))
      (node (ref "J10L") (pin "0") (pinfunction "GND_0") (pintype "passive"))
      (node (ref "J10L") (pin "11") (pinfunction "11_11") (pintype "passive"))
      (node (ref "J10L") (pin "17") (pinfunction "17_17") (pintype "passive"))
      (node (ref "J10L") (pin "2") (pinfunction "2_2") (pintype "passive"))
      (node (ref "J10L") (pin "5") (pinfunction "5_5") (pintype "passive"))
      (node (ref "J10L") (pin "8") (pinfunction "8_8") (pintype "passive"))
      (node (ref "JP10L") (pin "1") (pintype "passive"))
      (node (ref "JP10L") (pin "10") (pintype "passive"))
      (node (ref "JP10L") (pin "13") (pintype "passive"))
      (node (ref "JP10L") (pin "16") (pintype "passive"))
      (node (ref "JP10L") (pin "19") (pintype "passive"))
      (node (ref "JP10L") (pin "22") (pintype "passive"))
      (node (ref "JP10L") (pin "36") (pintype "passive"))
      (node (ref "JP10L") (pin "37") (pintype "passive"))
      (node (ref "JP10L") (pin "4") (pintype "passive"))
      (node (ref "JP10L") (pin "41") (pintype "passive"))
      (node (ref "JP10L") (pin "7") (pintype "passive"))
      (node (ref "Q12L") (pin "2") (pinfunction "S_2") (pintype "passive"))
      (node (ref "Q13L") (pin "2") (pinfunction "S_2") (pintype "passive"))
      (node (ref "Q14L") (pin "2") (pinfunction "S_2") (pintype "passive"))
      (node (ref "Q17L") (pin "2") (pinfunction "S_2") (pintype "passive"))
      (node (ref "Q18L") (pin "2") (pinfunction "S_2") (pintype "passive"))
      (node (ref "R13L") (pin "2") (pinfunction "2_2") (pintype "passive"))
      (node (ref "R14L") (pin "2") (pinfunction "2_2") (pintype "passive"))
      (node (ref "R18L") (pin "1") (pinfunction "1_1") (pintype "passive"))
      (node (ref "R24L") (pin "1") (pinfunction "1_1") (pintype "passive"))
      (node (ref "R25L") (pin "2") (pinfunction "B_2") (pintype "bidirectional"))
      (node (ref "U10L") (pin "2") (pinfunction "GND_2") (pintype "power_in"))
    )
    (net (code "94") (name "Net-(J10L-Pad13)") (class "Default")
      (node (ref "J10L") (pin "13") (pinfunction "13_13") (pintype "passive"))
      (node (ref "R31L") (pin "1") (pinfunction "1_1") (pintype "passive"))
    )
    (net (code "95") (name "Net-(J10L-Pad19)") (class "Default")
      (node (ref "J10L") (pin "19") (pinfunction "19_19") (pintype "passive"))
      (node (ref "R32L") (pin "1") (pinfunction "1_1") (pintype "passive"))
    )
    (net (code "96") (name "Net-(Q10L-G)") (class "Default")
      (node (ref "C14L") (pin "2") (pinfunction "2_2") (pintype "passive"))
      (node (ref "Q10L") (pin "4") (pinfunction "G_4") (pintype "passive"))
      (node (ref "R11L") (pin "1") (pinfunction "1_1") (pintype "passive"))
      (node (ref "R15L") (pin "1") (pinfunction "1_1") (pintype "passive"))
    )
    (net (code "97") (name "Net-(Q11L-G)") (class "Default")
      (node (ref "C19L") (pin "2") (pinfunction "2_2") (pintype "passive"))
      (node (ref "Q11L") (pin "4") (pinfunction "G_4") (pintype "passive"))
      (node (ref "R16L") (pin "1") (pinfunction "1_1") (pintype "passive"))
      (node (ref "R19L") (pin "1") (pinfunction "1_1") (pintype "passive"))
    )
    (net (code "98") (name "Net-(Q12L-D)") (class "Default")
      (node (ref "Q12L") (pin "3") (pinfunction "D_3") (pintype "passive"))
      (node (ref "Q13L") (pin "1") (pinfunction "G_1") (pintype "passive"))
      (node (ref "R15L") (pin "2") (pinfunction "2_2") (pintype "passive"))
    )
    (net (code "99") (name "Net-(Q13L-D)") (class "Default")
      (node (ref "Q13L") (pin "3") (pinfunction "D_3") (pintype "passive"))
      (node (ref "Q14L") (pin "1") (pinfunction "G_1") (pintype "passive"))
      (node (ref "R17L") (pin "1") (pinfunction "1_1") (pintype "passive"))
    )
    (net (code "100") (name "Net-(Q14L-D)") (class "Default")
      (node (ref "Q14L") (pin "3") (pinfunction "D_3") (pintype "passive"))
      (node (ref "R19L") (pin "2") (pinfunction "2_2") (pintype "passive"))
    )
    (net (code "101") (name "P3.3V") (class "Default")
      (node (ref "C10L") (pin "1") (pinfunction "1_1") (pintype "passive"))
      (node (ref "Q15L") (pin "1") (pinfunction "G_1") (pintype "passive"))
      (node (ref "Q16L") (pin "1") (pinfunction "G_1") (pintype "passive"))
      (node (ref "R20L") (pin "1") (pinfunction "1_1") (pintype "passive"))
      (node (ref "R23L") (pin "1") (pinfunction "1_1") (pintype "passive"))
    )
    (net (code "102") (name "P3.3V_DELAYED") (class "Default")
      (node (ref "C14L") (pin "1") (pinfunction "1_1") (pintype "passive"))
      (node (ref "Q10L") (pin "1") (pinfunction "S_1") (pintype "passive"))
      (node (ref "Q10L") (pin "2") (pinfunction "S_2") (pintype "passive"))
      (node (ref "Q10L") (pin "3") (pinfunction "S_3") (pintype "passive"))
      (node (ref "R11L") (pin "2") (pinfunction "2_2") (pintype "passive"))
      (node (ref "R12L") (pin "2") (pinfunction "2_2") (pintype "passive"))
      (node (ref "R29L") (pin "1") (pinfunction "1_1") (pintype "passive"))
      (node (ref "R30L") (pin "1") (pinfunction "1_1") (pintype "passive"))
    )
    (net (code "103") (name "P5.0V_DELAYED") (class "Default")
      (node (ref "C15L") (pin "1") (pinfunction "1_1") (pintype "passive"))
      (node (ref "F10L") (pin "1") (pinfunction "1_1") (pintype "bidirectional"))
      (node (ref "R21L") (pin "1") (pinfunction "1_1") (pintype "passive"))
      (node (ref "R22L") (pin "1") (pinfunction "1_1") (pintype "passive"))
      (node (ref "U10L") (pin "4") (pinfunction "VIN_4") (pintype "passive"))
    )
    (net (code "104") (name "VDDSOC_CAP") (class "Default")
      (node (ref "C20L") (pin "1") (pinfunction "1_1") (pintype "passive"))
      (node (ref "C21L") (pin "1") (pinfunction "1_1") (pintype "passive"))
      (node (ref "U100") (pin "L7") (pinfunction "HDMI_VP_L7") (pintype "power_in"))
    )
    (net (code "105") (name "VDD_HIGH_CAP") (class "Default")
      (node (ref "C11L") (pin "1") (pinfunction "1_1") (pintype "passive"))
      (node (ref "C22L") (pin "1") (pinfunction "1_1") (pintype "passive"))
      (node (ref "C23L") (pin "1") (pinfunction "1_1") (pintype "passive"))
      (node (ref "U100") (pin "M7") (pinfunction "HDMI_VPH_M7") (pintype "power_in"))
      (node (ref "U100") (pin "V7") (pinfunction "NVCC_LVDS2P5_V7") (pintype "power_in"))
    )
    (net (code "106") (name "unconnected-(J10L-Pad14)") (class "Default")
      (node (ref "J10L") (pin "14") (pinfunction "14_14") (pintype "passive"))
    )
    (net (code "107") (name "unconnected-(U100D-CSI0_DAT14-PadM4)") (class "Default")
      (node (ref "U100") (pin "M4") (pinfunction "CSI0_DAT14_M4") (pintype "bidirectional"))
    )
    (net (code "108") (name "unconnected-(U100D-CSI0_DAT15-PadM5)") (class "Default")
      (node (ref "U100") (pin "M5") (pinfunction "CSI0_DAT15_M5") (pintype "bidirectional"))
    )
    (net (code "109") (name "unconnected-(U100D-CSI0_DAT18-PadM6)") (class "Default")
      (node (ref "U100") (pin "M6") (pinfunction "CSI0_DAT18_M6") (pintype "bidirectional"))
    )
    (net (code "110") (name "unconnected-(U100D-CSI0_DAT19-PadL6)") (class "Default")
      (node (ref "U100") (pin "L6") (pinfunction "CSI0_DAT19_L6") (pintype "bidirectional"))
    )
    (net (code "111") (name "unconnected-(U100D-CSI0_PIXCLK-PadP1)") (class "Default")
      (node (ref "U100") (pin "P1") (pinfunction "CSI0_PIXCLK_P1") (pintype "bidirectional"))
    )
    (net (code "112") (name "unconnected-(U100D-CSI_CLK0M-PadF4)") (class "Default")
      (node (ref "U100") (pin "F4") (pinfunction "CSI_CLK0M_F4") (pintype "input+no_connect"))
    )
    (net (code "113") (name "unconnected-(U100D-CSI_CLK0P-PadF3)") (class "Default")
      (node (ref "U100") (pin "F3") (pinfunction "CSI_CLK0P_F3") (pintype "input+no_connect"))
    )
    (net (code "114") (name "unconnected-(U100D-CSI_D0M-PadE4)") (class "Default")
      (node (ref "U100") (pin "E4") (pinfunction "CSI_D0M_E4") (pintype "input+no_connect"))
    )
    (net (code "115") (name "unconnected-(U100D-CSI_D0P-PadE3)") (class "Default")
      (node (ref "U100") (pin "E3") (pinfunction "CSI_D0P_E3") (pintype "input+no_connect"))
    )
    (net (code "116") (name "unconnected-(U100D-CSI_D1M-PadD1)") (class "Default")
      (node (ref "U100") (pin "D1") (pinfunction "CSI_D1M_D1") (pintype "input+no_connect"))
    )
    (net (code "117") (name "unconnected-(U100D-CSI_D1P-PadD2)") (class "Default")
      (node (ref "U100") (pin "D2") (pinfunction "CSI_D1P_D2") (pintype "input+no_connect"))
    )
    (net (code "118") (name "unconnected-(U100D-CSI_D2M-PadE1)") (class "Default")
      (node (ref "U100") (pin "E1") (pinfunction "CSI_D2M_E1") (pintype "input+no_connect"))
    )
    (net (code "119") (name "unconnected-(U100D-CSI_D2P-PadE2)") (class "Default")
      (node (ref "U100") (pin "E2") (pinfunction "CSI_D2P_E2") (pintype "input+no_connect"))
    )
    (net (code "120") (name "unconnected-(U100D-CSI_D3M-PadF2)") (class "Default")
      (node (ref "U100") (pin "F2") (pinfunction "CSI_D3M_F2") (pintype "input+no_connect"))
    )
    (net (code "121") (name "unconnected-(U100D-CSI_D3P-PadF1)") (class "Default")
      (node (ref "U100") (pin "F1") (pinfunction "CSI_D3P_F1") (pintype "input+no_connect"))
    )
    (net (code "122") (name "unconnected-(U100D-DI0_DISP_CLK-PadN19)") (class "Default")
      (node (ref "U100") (pin "N19") (pinfunction "DI0_DISP_CLK_N19") (pintype "bidirectional"))
    )
    (net (code "123") (name "unconnected-(U100D-DSI_CLK0M-PadH3)") (class "Default")
      (node (ref "U100") (pin "H3") (pinfunction "DSI_CLK0M_H3") (pintype "output"))
    )
    (net (code "124") (name "unconnected-(U100D-DSI_CLK0P-PadH4)") (class "Default")
      (node (ref "U100") (pin "H4") (pinfunction "DSI_CLK0P_H4") (pintype "output"))
    )
    (net (code "125") (name "unconnected-(U100D-DSI_D0M-PadG2)") (class "Default")
      (node (ref "U100") (pin "G2") (pinfunction "DSI_D0M_G2") (pintype "output"))
    )
    (net (code "126") (name "unconnected-(U100D-DSI_D0P-PadG1)") (class "Default")
      (node (ref "U100") (pin "G1") (pinfunction "DSI_D0P_G1") (pintype "output"))
    )
    (net (code "127") (name "unconnected-(U100D-DSI_D1M-PadH2)") (class "Default")
      (node (ref "U100") (pin "H2") (pinfunction "DSI_D1M_H2") (pintype "output"))
    )
    (net (code "128") (name "unconnected-(U100D-DSI_D1P-PadH1)") (class "Default")
      (node (ref "U100") (pin "H1") (pinfunction "DSI_D1P_H1") (pintype "output"))
    )
    (net (code "129") (name "unconnected-(U100H-LVDS0_TX3_N-PadW2)") (class "Default")
      (node (ref "U100") (pin "W2") (pinfunction "LVDS0_TX3_N_W2") (pintype "output"))
    )
    (net (code "130") (name "unconnected-(U100H-LVDS0_TX3_P-PadW1)") (class "Default")
      (node (ref "U100") (pin "W1") (pinfunction "LVDS0_TX3_P_W1") (pintype "output"))
    )
    (net (code "131") (name "unconnected-(U100H-LVDS1_TX3_N-PadAA3)") (class "Default")
      (node (ref "U100") (pin "AA3") (pinfunction "LVDS1_TX3_N_AA3") (pintype "output"))
    )
    (net (code "132") (name "unconnected-(U100H-LVDS1_TX3_P-PadAA4)") (class "Default")
      (node (ref "U100") (pin "AA4") (pinfunction "LVDS1_TX3_P_AA4") (pintype "output"))
    )
  )
)
